# BULLBERRYCPP_REV1_0_2025-06-09.net
KiCad netlist of a schematic drawn in EasyEDA Pro
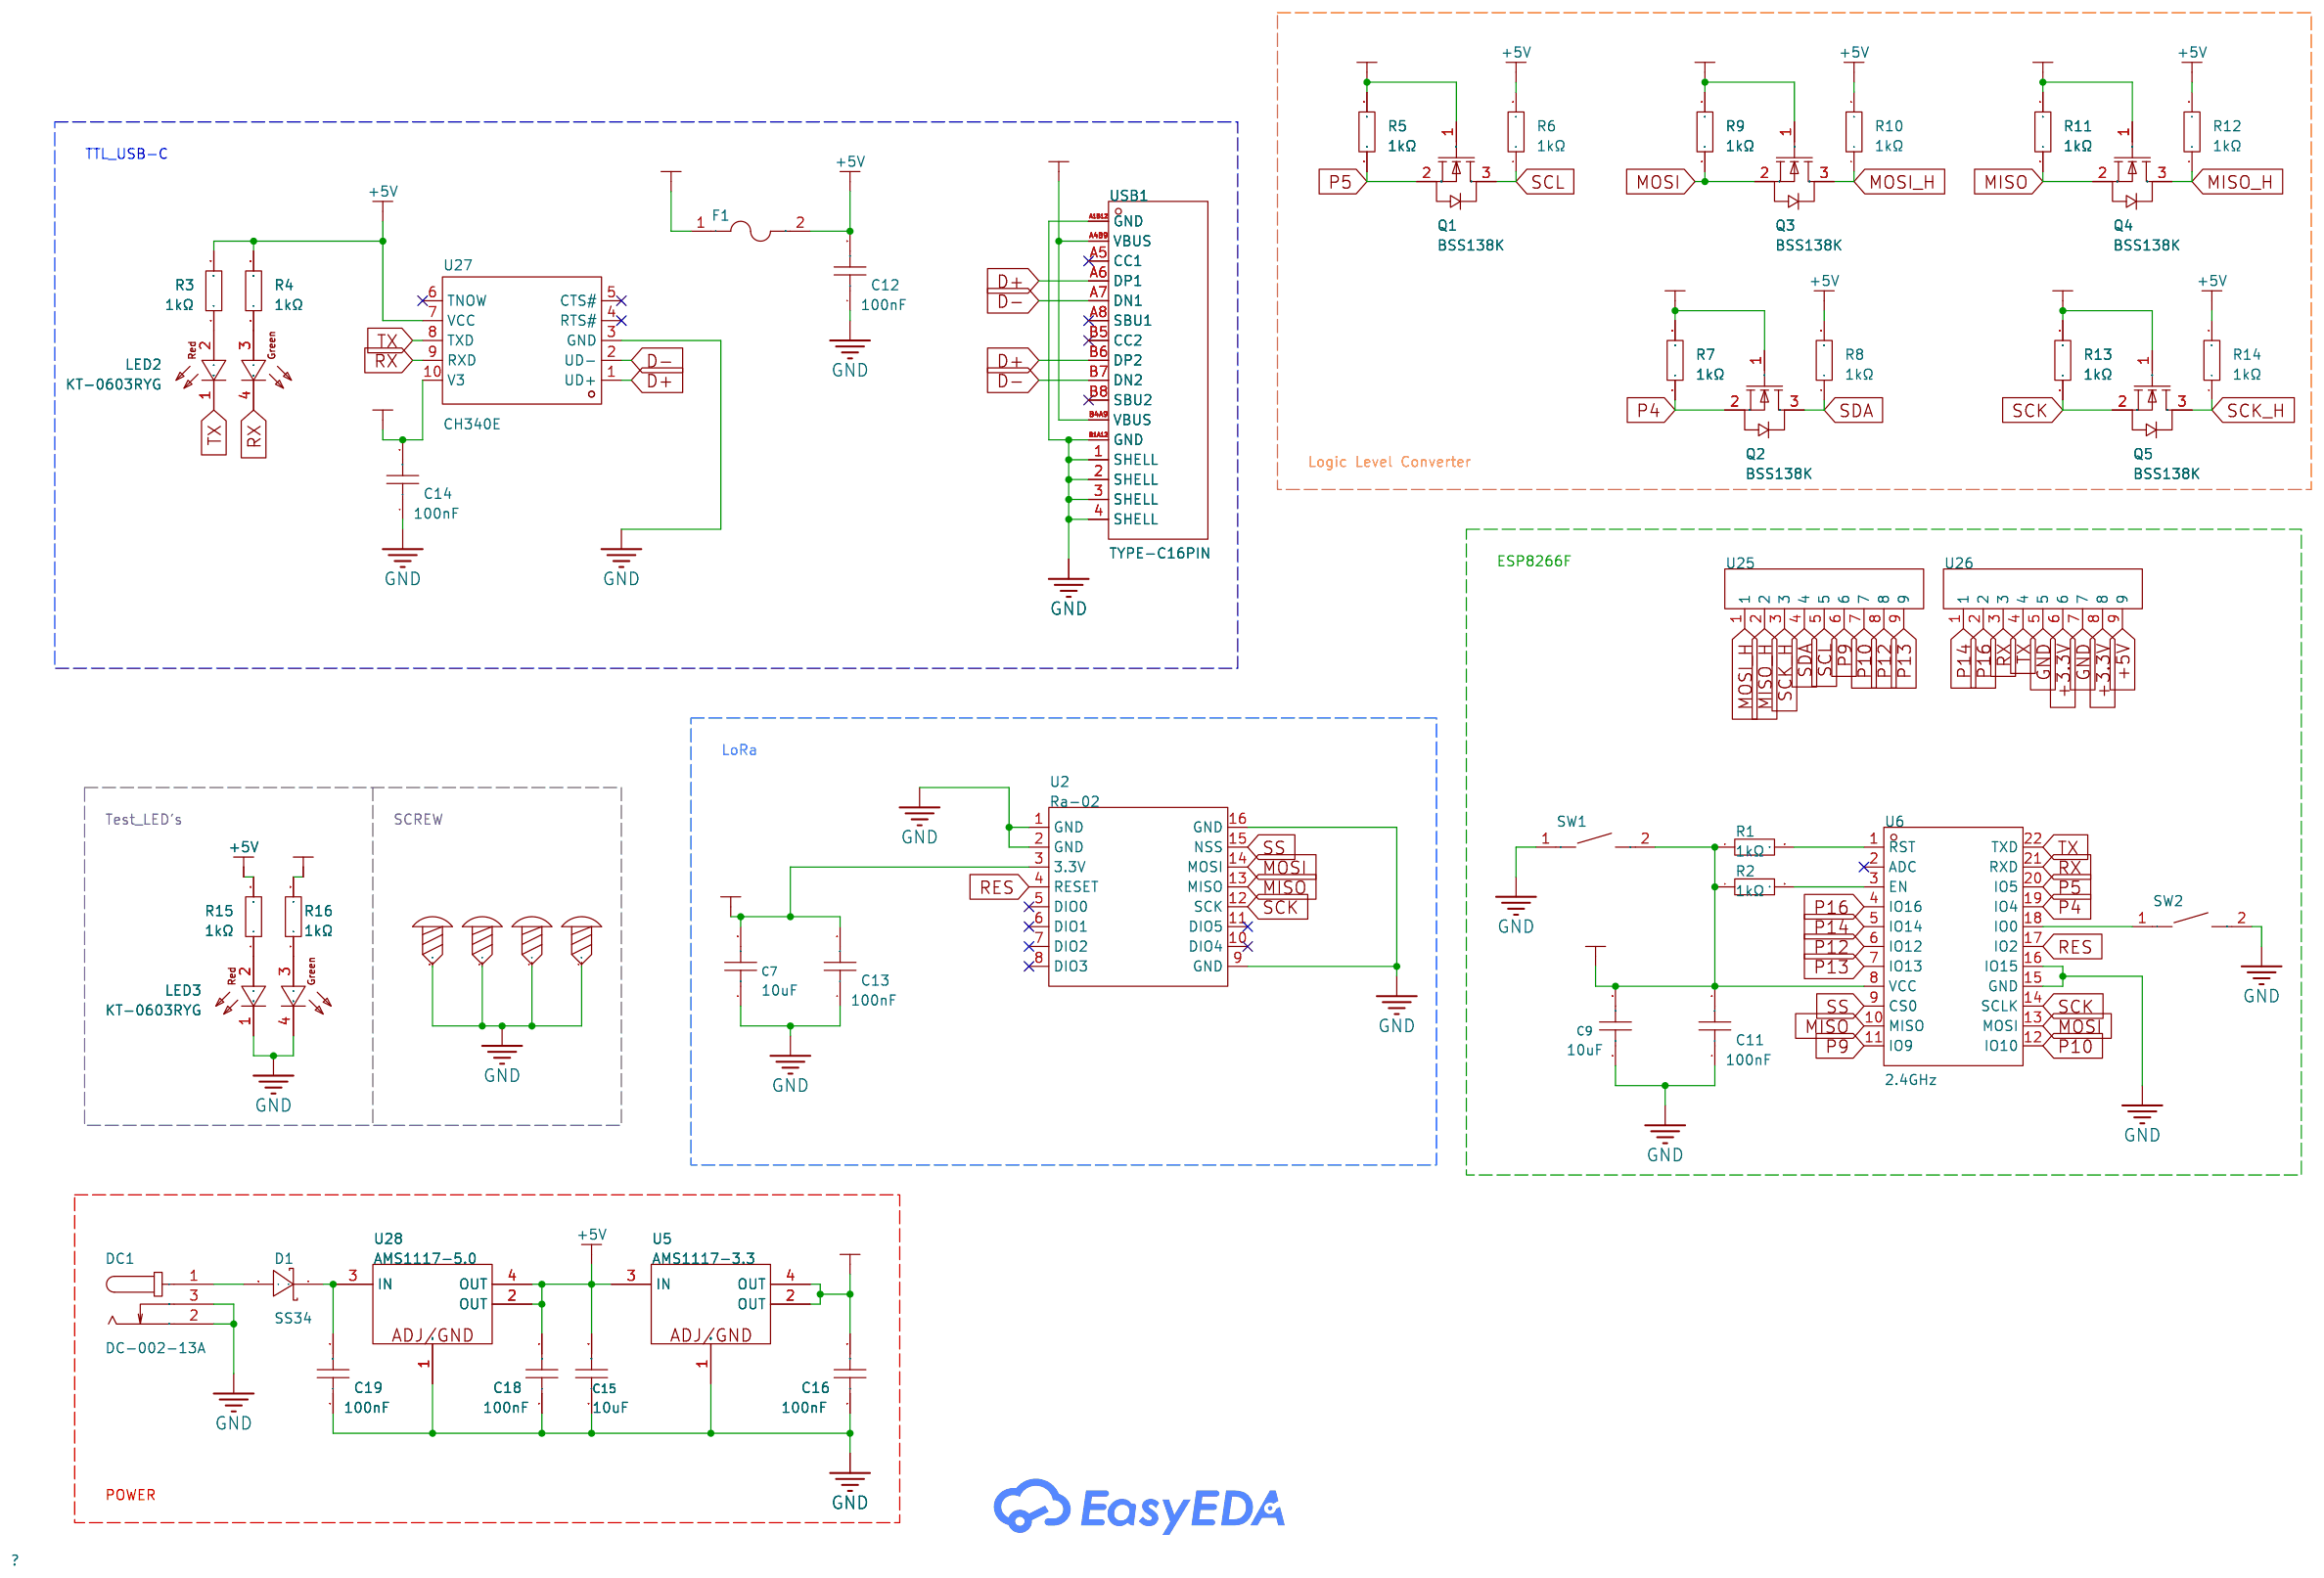
[diagram p0: schematic sheet]

(export (version "E")
  (design (tool "Eeschema 10.0.6"))
  (components
    (comp (ref "C7")
      (value "10uF")
      (footprint "easyedapro:C0603")
      (fields
        (field (name "Manufacturer Part") "CL10A106MA8NRNC")
        (field (name "Manufacturer") "SAMSUNG(三星)")
      )
      (libsource (lib "easyedapro") (part "CL10A106MA8NRNC"))
    )
    (comp (ref "C9")
      (value "10uF")
      (footprint "easyedapro:C0603")
      (fields
        (field (name "Manufacturer Part") "CL10A106MA8NRNC")
        (field (name "Manufacturer") "SAMSUNG(三星)")
      )
      (libsource (lib "easyedapro") (part "CL10A106MA8NRNC"))
    )
    (comp (ref "C11")
      (value "100nF")
      (footprint "easyedapro:C0603")
      (description "Capacitance:100nF Tolerance:±10% Tolerance:±10% Voltage Rating:50V Temperature Coefficient:X7R")
      (fields
        (field (name "Manufacturer Part") "CC0603KRX7R9BB104")
        (field (name "Manufacturer") "YAGEO(国巨)")
      )
      (libsource (lib "easyedapro") (part "CC0603KRX7R9BB104"))
    )
    (comp (ref "C12")
      (value "100nF")
      (footprint "easyedapro:C0603")
      (description "Capacitance:100nF Tolerance:±10% Tolerance:±10% Voltage Rating:50V Temperature Coefficient:X7R")
      (fields
        (field (name "Manufacturer Part") "CC0603KRX7R9BB104")
        (field (name "Manufacturer") "YAGEO(国巨)")
      )
      (libsource (lib "easyedapro") (part "CC0603KRX7R9BB104"))
    )
    (comp (ref "C13")
      (value "100nF")
      (footprint "easyedapro:C0603")
      (description "Capacitance:100nF Tolerance:±10% Tolerance:±10% Voltage Rating:50V Temperature Coefficient:X7R")
      (fields
        (field (name "Manufacturer Part") "CC0603KRX7R9BB104")
        (field (name "Manufacturer") "YAGEO(国巨)")
      )
      (libsource (lib "easyedapro") (part "CC0603KRX7R9BB104"))
    )
    (comp (ref "C14")
      (value "100nF")
      (footprint "easyedapro:C0603")
      (description "Capacitance:100nF Tolerance:±10% Tolerance:±10% Voltage Rating:50V Temperature Coefficient:X7R")
      (fields
        (field (name "Manufacturer Part") "CC0603KRX7R9BB104")
        (field (name "Manufacturer") "YAGEO(国巨)")
      )
      (libsource (lib "easyedapro") (part "CC0603KRX7R9BB104"))
    )
    (comp (ref "C15")
      (value "10uF")
      (footprint "easyedapro:C0603")
      (fields
        (field (name "Manufacturer Part") "CL10A106MA8NRNC")
        (field (name "Manufacturer") "SAMSUNG(三星)")
      )
      (libsource (lib "easyedapro") (part "CL10A106MA8NRNC"))
    )
    (comp (ref "C16")
      (value "100nF")
      (footprint "easyedapro:C0603")
      (description "Capacitance:100nF Tolerance:±10% Tolerance:±10% Voltage Rating:50V Temperature Coefficient:X7R")
      (fields
        (field (name "Manufacturer Part") "CC0603KRX7R9BB104")
        (field (name "Manufacturer") "YAGEO(国巨)")
      )
      (libsource (lib "easyedapro") (part "CC0603KRX7R9BB104"))
    )
    (comp (ref "C18")
      (value "100nF")
      (footprint "easyedapro:C0603")
      (description "Capacitance:100nF Tolerance:±10% Tolerance:±10% Voltage Rating:50V Temperature Coefficient:X7R")
      (fields
        (field (name "Manufacturer Part") "CC0603KRX7R9BB104")
        (field (name "Manufacturer") "YAGEO(国巨)")
      )
      (libsource (lib "easyedapro") (part "CC0603KRX7R9BB104"))
    )
    (comp (ref "C19")
      (value "100nF")
      (footprint "easyedapro:C0603")
      (description "Capacitance:100nF Tolerance:±10% Tolerance:±10% Voltage Rating:50V Temperature Coefficient:X7R")
      (fields
        (field (name "Manufacturer Part") "CC0603KRX7R9BB104")
        (field (name "Manufacturer") "YAGEO(国巨)")
      )
      (libsource (lib "easyedapro") (part "CC0603KRX7R9BB104"))
    )
    (comp (ref "D1")
      (value "SS34")
      (footprint "easyedapro:SMA_L4.3-W2.6-LS5.2-RD")
      (fields (field (name "Manufacturer") "MDD(辰达半导体)"))
      (libsource (lib "easyedapro") (part "SS34_C8678"))
    )
    (comp (ref "DC1")
      (value "DC-002-13A")
      (footprint "easyedapro:DC-IN-TH_DC-002-13A")
      (fields (field (name "Manufacturer") "韩国韩荣"))
      (libsource (lib "easyedapro") (part "DC-002-13A"))
    )
    (comp (ref "F1")
      (value "JFC0603-0500FS")
      (footprint "easyedapro:F0603")
      (fields (field (name "Manufacturer") "JDTfuse(集电通)"))
      (libsource (lib "easyedapro") (part "JFC0603-0500FS"))
    )
    (comp (ref "LED2")
      (value "KT-0603RYG")
      (footprint "easyedapro:LED-SMD_4P-L1.6-W1.5_KT-0603RG")
      (fields (field (name "Manufacturer") "KENTO"))
      (libsource (lib "easyedapro") (part "KT-0603RG"))
    )
    (comp (ref "LED3")
      (value "KT-0603RYG")
      (footprint "easyedapro:LED-SMD_4P-L1.6-W1.5_KT-0603RG")
      (fields (field (name "Manufacturer") "KENTO"))
      (libsource (lib "easyedapro") (part "KT-0603RG"))
    )
    (comp (ref "Q1")
      (value "BSS138K")
      (footprint "easyedapro:SOT-23-3_L2.9-W1.3-P0.95-LS2.4-BR")
      (fields (field (name "Manufacturer") "PAKER(派克微)"))
      (libsource (lib "easyedapro") (part "BSS138K_C18221542"))
    )
    (comp (ref "Q2")
      (value "BSS138K")
      (footprint "easyedapro:SOT-23-3_L2.9-W1.3-P0.95-LS2.4-BR")
      (fields (field (name "Manufacturer") "PAKER(派克微)"))
      (libsource (lib "easyedapro") (part "BSS138K_C18221542"))
    )
    (comp (ref "Q3")
      (value "BSS138K")
      (footprint "easyedapro:SOT-23-3_L2.9-W1.3-P0.95-LS2.4-BR")
      (fields (field (name "Manufacturer") "PAKER(派克微)"))
      (libsource (lib "easyedapro") (part "BSS138K_C18221542"))
    )
    (comp (ref "Q4")
      (value "BSS138K")
      (footprint "easyedapro:SOT-23-3_L2.9-W1.3-P0.95-LS2.4-BR")
      (fields (field (name "Manufacturer") "PAKER(派克微)"))
      (libsource (lib "easyedapro") (part "BSS138K_C18221542"))
    )
    (comp (ref "Q5")
      (value "BSS138K")
      (footprint "easyedapro:SOT-23-3_L2.9-W1.3-P0.95-LS2.4-BR")
      (fields (field (name "Manufacturer") "PAKER(派克微)"))
      (libsource (lib "easyedapro") (part "BSS138K_C18221542"))
    )
    (comp (ref "R1")
      (value "1kΩ")
      (footprint "easyedapro:R0603")
      (fields
        (field (name "Manufacturer Part") "0603WAF1001T5E")
        (field (name "Manufacturer") "UNI-ROYAL(厚声)")
      )
      (libsource (lib "easyedapro") (part "0603WAF1001T5E"))
    )
    (comp (ref "R2")
      (value "1kΩ")
      (footprint "easyedapro:R0603")
      (fields
        (field (name "Manufacturer Part") "0603WAF1001T5E")
        (field (name "Manufacturer") "UNI-ROYAL(厚声)")
      )
      (libsource (lib "easyedapro") (part "0603WAF1001T5E"))
    )
    (comp (ref "R3")
      (value "1kΩ")
      (footprint "easyedapro:R0603")
      (fields
        (field (name "Manufacturer Part") "0603WAF1001T5E")
        (field (name "Manufacturer") "UNI-ROYAL(厚声)")
      )
      (libsource (lib "easyedapro") (part "0603WAF1001T5E"))
    )
    (comp (ref "R4")
      (value "1kΩ")
      (footprint "easyedapro:R0603")
      (fields
        (field (name "Manufacturer Part") "0603WAF1001T5E")
        (field (name "Manufacturer") "UNI-ROYAL(厚声)")
      )
      (libsource (lib "easyedapro") (part "0603WAF1001T5E"))
    )
    (comp (ref "R5")
      (value "1kΩ")
      (footprint "easyedapro:R0603")
      (fields
        (field (name "Manufacturer Part") "0603WAF1001T5E")
        (field (name "Manufacturer") "UNI-ROYAL(厚声)")
      )
      (libsource (lib "easyedapro") (part "0603WAF1001T5E"))
    )
    (comp (ref "R6")
      (value "1kΩ")
      (footprint "easyedapro:R0603")
      (fields
        (field (name "Manufacturer Part") "0603WAF1001T5E")
        (field (name "Manufacturer") "UNI-ROYAL(厚声)")
      )
      (libsource (lib "easyedapro") (part "0603WAF1001T5E"))
    )
    (comp (ref "R7")
      (value "1kΩ")
      (footprint "easyedapro:R0603")
      (fields
        (field (name "Manufacturer Part") "0603WAF1001T5E")
        (field (name "Manufacturer") "UNI-ROYAL(厚声)")
      )
      (libsource (lib "easyedapro") (part "0603WAF1001T5E"))
    )
    (comp (ref "R8")
      (value "1kΩ")
      (footprint "easyedapro:R0603")
      (fields
        (field (name "Manufacturer Part") "0603WAF1001T5E")
        (field (name "Manufacturer") "UNI-ROYAL(厚声)")
      )
      (libsource (lib "easyedapro") (part "0603WAF1001T5E"))
    )
    (comp (ref "R9")
      (value "1kΩ")
      (footprint "easyedapro:R0603")
      (fields
        (field (name "Manufacturer Part") "0603WAF1001T5E")
        (field (name "Manufacturer") "UNI-ROYAL(厚声)")
      )
      (libsource (lib "easyedapro") (part "0603WAF1001T5E"))
    )
    (comp (ref "R10")
      (value "1kΩ")
      (footprint "easyedapro:R0603")
      (fields
        (field (name "Manufacturer Part") "0603WAF1001T5E")
        (field (name "Manufacturer") "UNI-ROYAL(厚声)")
      )
      (libsource (lib "easyedapro") (part "0603WAF1001T5E"))
    )
    (comp (ref "R11")
      (value "1kΩ")
      (footprint "easyedapro:R0603")
      (fields
        (field (name "Manufacturer Part") "0603WAF1001T5E")
        (field (name "Manufacturer") "UNI-ROYAL(厚声)")
      )
      (libsource (lib "easyedapro") (part "0603WAF1001T5E"))
    )
    (comp (ref "R12")
      (value "1kΩ")
      (footprint "easyedapro:R0603")
      (fields
        (field (name "Manufacturer Part") "0603WAF1001T5E")
        (field (name "Manufacturer") "UNI-ROYAL(厚声)")
      )
      (libsource (lib "easyedapro") (part "0603WAF1001T5E"))
    )
    (comp (ref "R13")
      (value "1kΩ")
      (footprint "easyedapro:R0603")
      (fields
        (field (name "Manufacturer Part") "0603WAF1001T5E")
        (field (name "Manufacturer") "UNI-ROYAL(厚声)")
      )
      (libsource (lib "easyedapro") (part "0603WAF1001T5E"))
    )
    (comp (ref "R14")
      (value "1kΩ")
      (footprint "easyedapro:R0603")
      (fields
        (field (name "Manufacturer Part") "0603WAF1001T5E")
        (field (name "Manufacturer") "UNI-ROYAL(厚声)")
      )
      (libsource (lib "easyedapro") (part "0603WAF1001T5E"))
    )
    (comp (ref "R15")
      (value "1kΩ")
      (footprint "easyedapro:R0603")
      (fields
        (field (name "Manufacturer Part") "0603WAF1001T5E")
        (field (name "Manufacturer") "UNI-ROYAL(厚声)")
      )
      (libsource (lib "easyedapro") (part "0603WAF1001T5E"))
    )
    (comp (ref "R16")
      (value "1kΩ")
      (footprint "easyedapro:R0603")
      (fields
        (field (name "Manufacturer Part") "0603WAF1001T5E")
        (field (name "Manufacturer") "UNI-ROYAL(厚声)")
      )
      (libsource (lib "easyedapro") (part "0603WAF1001T5E"))
    )
    (comp (ref "SCREW1")
      (value "~")
      (footprint "easyedapro:Screw-Hole-M2")
      (libsource (lib "easyedapro") (part "Screw-Hole"))
    )
    (comp (ref "SCREW2")
      (value "~")
      (footprint "easyedapro:Screw-Hole-M2")
      (libsource (lib "easyedapro") (part "Screw-Hole"))
    )
    (comp (ref "SCREW3")
      (value "~")
      (footprint "easyedapro:Screw-Hole-M2")
      (libsource (lib "easyedapro") (part "Screw-Hole"))
    )
    (comp (ref "SCREW4")
      (value "~")
      (footprint "easyedapro:Screw-Hole-M2")
      (libsource (lib "easyedapro") (part "Screw-Hole"))
    )
    (comp (ref "SW1")
      (value "TS-1088-AR02016")
      (footprint "easyedapro:SW-SMD_L3.9-W3.0-P4.45")
      (fields (field (name "Manufacturer") "XUNPU(讯普)"))
      (libsource (lib "easyedapro") (part "TS-1088-AR02016"))
    )
    (comp (ref "SW2")
      (value "TS-1088-AR02016")
      (footprint "easyedapro:SW-SMD_L3.9-W3.0-P4.45")
      (fields (field (name "Manufacturer") "XUNPU(讯普)"))
      (libsource (lib "easyedapro") (part "TS-1088-AR02016"))
    )
    (comp (ref "U2")
      (value "Ra-02")
      (footprint "easyedapro:WIRELM-SMD_RA-02-BL")
      (fields (field (name "Manufacturer") "Ai-Thinker(安信可)"))
      (libsource (lib "easyedapro") (part "RA-02"))
    )
    (comp (ref "U5")
      (value "AMS1117-3.3")
      (footprint "easyedapro:SOT-223-3_L6.4-W3.5-P2.30-LS7.0-BR")
      (fields (field (name "Manufacturer") "国芯佳品"))
      (libsource (lib "easyedapro") (part "AMS1117-3.3_C2992570"))
    )
    (comp (ref "U6")
      (value "2.4GHz")
      (footprint "easyedapro:WIRELM-SMD_ESP-12F")
      (fields (field (name "Manufacturer Part") "ESP-12F") (field (name "Manufacturer") "DOIT(四博智联)"))
      (libsource (lib "easyedapro") (part "ESP-12F"))
    )
    (comp (ref "U25")
      (value "DIP插件")
      (footprint "easyedapro:HDR-TH_9P-P2.00-V-F")
      (libsource (lib "easyedapro") (part "DIP-1"))
    )
    (comp (ref "U26")
      (value "DIP插件")
      (footprint "easyedapro:HDR-TH_9P-P2.00-V-F")
      (libsource (lib "easyedapro") (part "DIP-1"))
    )
    (comp (ref "U27")
      (value "CH340E")
      (footprint "easyedapro:MSOP-10_L3.0-W3.0-P0.50-LS5.0-BL")
      (fields (field (name "Manufacturer") "WCH(南京沁恒)"))
      (libsource (lib "easyedapro") (part "CH340E"))
    )
    (comp (ref "U28")
      (value "AMS1117-5.0")
      (footprint "easyedapro:SOT-223-3_L6.4-W3.5-P2.30-LS7.0-BR")
      (fields (field (name "Manufacturer") "国芯佳品"))
      (libsource (lib "easyedapro") (part "AMS1117-5.0_C2992571"))
    )
    (comp (ref "USB1")
      (value "TYPE-C16PIN")
      (footprint "easyedapro:USB-C-SMD_TYPE-C16PIN")
      (fields (field (name "Manufacturer") "SHOU HAN(首韩)"))
      (libsource (lib "easyedapro") (part "TYPE-C16PIN"))
    )
  )
  (nets
    (net (code "1") (name "+3.3V") (class "Default")
      (node (ref "C11") (pin "2") (pinfunction "2_2") (pintype "unspecified"))
      (node (ref "C13") (pin "2") (pinfunction "2_2") (pintype "unspecified"))
      (node (ref "C14") (pin "2") (pinfunction "2_2") (pintype "unspecified"))
      (node (ref "C16") (pin "2") (pinfunction "2_2") (pintype "unspecified"))
      (node (ref "C7") (pin "2") (pinfunction "2_2") (pintype "input"))
      (node (ref "C9") (pin "2") (pinfunction "2_2") (pintype "input"))
      (node (ref "Q1") (pin "1") (pinfunction "G_1") (pintype "unspecified"))
      (node (ref "Q2") (pin "1") (pinfunction "G_1") (pintype "unspecified"))
      (node (ref "Q3") (pin "1") (pinfunction "G_1") (pintype "unspecified"))
      (node (ref "Q4") (pin "1") (pinfunction "G_1") (pintype "unspecified"))
      (node (ref "Q5") (pin "1") (pinfunction "G_1") (pintype "unspecified"))
      (node (ref "R1") (pin "1") (pinfunction "1_1") (pintype "input"))
      (node (ref "R11") (pin "2") (pinfunction "2_2") (pintype "input"))
      (node (ref "R13") (pin "2") (pinfunction "2_2") (pintype "input"))
      (node (ref "R16") (pin "2") (pinfunction "2_2") (pintype "input"))
      (node (ref "R2") (pin "1") (pinfunction "1_1") (pintype "input"))
      (node (ref "R5") (pin "2") (pinfunction "2_2") (pintype "input"))
      (node (ref "R7") (pin "2") (pinfunction "2_2") (pintype "input"))
      (node (ref "R9") (pin "2") (pinfunction "2_2") (pintype "input"))
      (node (ref "SW1") (pin "2") (pinfunction "2_2") (pintype "unspecified"))
      (node (ref "U2") (pin "3") (pinfunction "3.3V_3") (pintype "unspecified"))
      (node (ref "U26") (pin "6") (pinfunction "6_6") (pintype "unspecified"))
      (node (ref "U26") (pin "8") (pinfunction "8_8") (pintype "unspecified"))
      (node (ref "U27") (pin "10") (pinfunction "V3_10") (pintype "unspecified"))
      (node (ref "U5") (pin "2") (pinfunction "OUT_2") (pintype "unspecified"))
      (node (ref "U5") (pin "4") (pinfunction "OUT_4") (pintype "unspecified"))
      (node (ref "U6") (pin "8") (pinfunction "VCC_8") (pintype "unspecified"))
    )
    (net (code "2") (name "+5V") (class "Default")
      (node (ref "C12") (pin "2") (pinfunction "2_2") (pintype "unspecified"))
      (node (ref "C15") (pin "2") (pinfunction "2_2") (pintype "input"))
      (node (ref "C18") (pin "2") (pinfunction "2_2") (pintype "unspecified"))
      (node (ref "F1") (pin "2") (pinfunction "2_2") (pintype "unspecified"))
      (node (ref "R10") (pin "2") (pinfunction "2_2") (pintype "input"))
      (node (ref "R12") (pin "2") (pinfunction "2_2") (pintype "input"))
      (node (ref "R14") (pin "2") (pinfunction "2_2") (pintype "input"))
      (node (ref "R15") (pin "2") (pinfunction "2_2") (pintype "input"))
      (node (ref "R3") (pin "2") (pinfunction "2_2") (pintype "input"))
      (node (ref "R4") (pin "2") (pinfunction "2_2") (pintype "input"))
      (node (ref "R6") (pin "2") (pinfunction "2_2") (pintype "input"))
      (node (ref "R8") (pin "2") (pinfunction "2_2") (pintype "input"))
      (node (ref "U26") (pin "9") (pinfunction "9_9") (pintype "unspecified"))
      (node (ref "U27") (pin "7") (pinfunction "VCC_7") (pintype "unspecified"))
      (node (ref "U28") (pin "2") (pinfunction "OUT_2") (pintype "unspecified"))
      (node (ref "U28") (pin "4") (pinfunction "OUT_4") (pintype "unspecified"))
      (node (ref "U5") (pin "3") (pinfunction "IN_3") (pintype "unspecified"))
    )
    (net (code "3") (name "D+") (class "Default")
      (node (ref "U27") (pin "1") (pinfunction "UD+_1") (pintype "unspecified"))
      (node (ref "USB1") (pin "A6") (pinfunction "DP1_A6") (pintype "unspecified"))
      (node (ref "USB1") (pin "B6") (pinfunction "DP2_B6") (pintype "unspecified"))
    )
    (net (code "4") (name "D-") (class "Default")
      (node (ref "U27") (pin "2") (pinfunction "UD-_2") (pintype "unspecified"))
      (node (ref "USB1") (pin "A7") (pinfunction "DN1_A7") (pintype "unspecified"))
      (node (ref "USB1") (pin "B7") (pinfunction "DN2_B7") (pintype "unspecified"))
    )
    (net (code "5") (name "GND") (class "Default")
      (node (ref "C11") (pin "1") (pinfunction "1_1") (pintype "unspecified"))
      (node (ref "C12") (pin "1") (pinfunction "1_1") (pintype "unspecified"))
      (node (ref "C13") (pin "1") (pinfunction "1_1") (pintype "unspecified"))
      (node (ref "C14") (pin "1") (pinfunction "1_1") (pintype "unspecified"))
      (node (ref "C15") (pin "1") (pinfunction "1_1") (pintype "input"))
      (node (ref "C16") (pin "1") (pinfunction "1_1") (pintype "unspecified"))
      (node (ref "C18") (pin "1") (pinfunction "1_1") (pintype "unspecified"))
      (node (ref "C19") (pin "1") (pinfunction "1_1") (pintype "unspecified"))
      (node (ref "C7") (pin "1") (pinfunction "1_1") (pintype "input"))
      (node (ref "C9") (pin "1") (pinfunction "1_1") (pintype "input"))
      (node (ref "DC1") (pin "2") (pinfunction "2_2") (pintype "unspecified"))
      (node (ref "DC1") (pin "3") (pinfunction "3_3") (pintype "unspecified"))
      (node (ref "LED3") (pin "1") (pinfunction "C_1") (pintype "input"))
      (node (ref "LED3") (pin "4") (pinfunction "C_4") (pintype "input"))
      (node (ref "SCREW1") (pin "1") (pinfunction "1_1") (pintype "input"))
      (node (ref "SCREW2") (pin "1") (pinfunction "1_1") (pintype "input"))
      (node (ref "SCREW3") (pin "1") (pinfunction "1_1") (pintype "input"))
      (node (ref "SCREW4") (pin "1") (pinfunction "1_1") (pintype "input"))
      (node (ref "SW1") (pin "1") (pinfunction "1_1") (pintype "unspecified"))
      (node (ref "SW2") (pin "2") (pinfunction "2_2") (pintype "unspecified"))
      (node (ref "U2") (pin "1") (pinfunction "GND_1") (pintype "unspecified"))
      (node (ref "U2") (pin "16") (pinfunction "GND_16") (pintype "unspecified"))
      (node (ref "U2") (pin "2") (pinfunction "GND_2") (pintype "unspecified"))
      (node (ref "U2") (pin "9") (pinfunction "GND_9") (pintype "unspecified"))
      (node (ref "U26") (pin "5") (pinfunction "5_5") (pintype "unspecified"))
      (node (ref "U26") (pin "7") (pinfunction "7_7") (pintype "unspecified"))
      (node (ref "U27") (pin "3") (pinfunction "GND_3") (pintype "unspecified"))
      (node (ref "U28") (pin "1") (pinfunction "ADJ/GND_1") (pintype "unspecified"))
      (node (ref "U5") (pin "1") (pinfunction "ADJ/GND_1") (pintype "unspecified"))
      (node (ref "U6") (pin "15") (pinfunction "GND_15") (pintype "unspecified"))
      (node (ref "U6") (pin "16") (pinfunction "IO15_16") (pintype "unspecified"))
      (node (ref "USB1") (pin "1") (pinfunction "SHELL_1") (pintype "unspecified"))
      (node (ref "USB1") (pin "2") (pinfunction "SHELL_2") (pintype "unspecified"))
      (node (ref "USB1") (pin "3") (pinfunction "SHELL_3") (pintype "unspecified"))
      (node (ref "USB1") (pin "4") (pinfunction "SHELL_4") (pintype "unspecified"))
      (node (ref "USB1") (pin "A1B12") (pinfunction "GND_A1B12") (pintype "unspecified"))
      (node (ref "USB1") (pin "B1A12") (pinfunction "GND_B1A12") (pintype "unspecified"))
    )
    (net (code "6") (name "MISO") (class "Default")
      (node (ref "Q4") (pin "2") (pinfunction "S_2") (pintype "unspecified"))
      (node (ref "R11") (pin "1") (pinfunction "1_1") (pintype "input"))
      (node (ref "U2") (pin "13") (pinfunction "MISO_13") (pintype "unspecified"))
      (node (ref "U6") (pin "10") (pinfunction "MISO_10") (pintype "unspecified"))
    )
    (net (code "7") (name "MISO_H") (class "Default")
      (node (ref "Q4") (pin "3") (pinfunction "D_3") (pintype "unspecified"))
      (node (ref "R12") (pin "1") (pinfunction "1_1") (pintype "input"))
      (node (ref "U25") (pin "2") (pinfunction "2_2") (pintype "unspecified"))
    )
    (net (code "8") (name "MOSI") (class "Default")
      (node (ref "Q3") (pin "2") (pinfunction "S_2") (pintype "unspecified"))
      (node (ref "R9") (pin "1") (pinfunction "1_1") (pintype "input"))
      (node (ref "U2") (pin "14") (pinfunction "MOSI_14") (pintype "unspecified"))
      (node (ref "U6") (pin "13") (pinfunction "MOSI_13") (pintype "unspecified"))
    )
    (net (code "9") (name "MOSI_H") (class "Default")
      (node (ref "Q3") (pin "3") (pinfunction "D_3") (pintype "unspecified"))
      (node (ref "R10") (pin "1") (pinfunction "1_1") (pintype "input"))
      (node (ref "U25") (pin "1") (pinfunction "1_1") (pintype "unspecified"))
    )
    (net (code "10") (name "Net-(D1-A)") (class "Default")
      (node (ref "D1") (pin "2") (pinfunction "A_2") (pintype "unspecified"))
      (node (ref "DC1") (pin "1") (pinfunction "1_1") (pintype "unspecified"))
    )
    (net (code "11") (name "Net-(D1-K)") (class "Default")
      (node (ref "C19") (pin "2") (pinfunction "2_2") (pintype "unspecified"))
      (node (ref "D1") (pin "1") (pinfunction "K_1") (pintype "unspecified"))
      (node (ref "U28") (pin "3") (pinfunction "IN_3") (pintype "unspecified"))
    )
    (net (code "12") (name "Net-(LED2-A-Pad2)") (class "Default")
      (node (ref "LED2") (pin "2") (pinfunction "A_2") (pintype "input"))
      (node (ref "R3") (pin "1") (pinfunction "1_1") (pintype "input"))
    )
    (net (code "13") (name "Net-(LED2-A-Pad3)") (class "Default")
      (node (ref "LED2") (pin "3") (pinfunction "A_3") (pintype "input"))
      (node (ref "R4") (pin "1") (pinfunction "1_1") (pintype "input"))
    )
    (net (code "14") (name "Net-(LED3-A-Pad2)") (class "Default")
      (node (ref "LED3") (pin "2") (pinfunction "A_2") (pintype "input"))
      (node (ref "R15") (pin "1") (pinfunction "1_1") (pintype "input"))
    )
    (net (code "15") (name "Net-(LED3-A-Pad3)") (class "Default")
      (node (ref "LED3") (pin "3") (pinfunction "A_3") (pintype "input"))
      (node (ref "R16") (pin "1") (pinfunction "1_1") (pintype "input"))
    )
    (net (code "16") (name "Net-(U6-EN)") (class "Default")
      (node (ref "R2") (pin "2") (pinfunction "2_2") (pintype "input"))
      (node (ref "U6") (pin "3") (pinfunction "EN_3") (pintype "unspecified"))
    )
    (net (code "17") (name "Net-(U6-IO0)") (class "Default")
      (node (ref "SW2") (pin "1") (pinfunction "1_1") (pintype "unspecified"))
      (node (ref "U6") (pin "18") (pinfunction "IO0_18") (pintype "unspecified"))
    )
    (net (code "18") (name "Net-(U6-RST)") (class "Default")
      (node (ref "R1") (pin "2") (pinfunction "2_2") (pintype "input"))
      (node (ref "U6") (pin "1") (pinfunction "RST_1") (pintype "unspecified"))
    )
    (net (code "19") (name "P4") (class "Default")
      (node (ref "Q2") (pin "2") (pinfunction "S_2") (pintype "unspecified"))
      (node (ref "R7") (pin "1") (pinfunction "1_1") (pintype "input"))
      (node (ref "U6") (pin "19") (pinfunction "IO4_19") (pintype "unspecified"))
    )
    (net (code "20") (name "P5") (class "Default")
      (node (ref "Q1") (pin "2") (pinfunction "S_2") (pintype "unspecified"))
      (node (ref "R5") (pin "1") (pinfunction "1_1") (pintype "input"))
      (node (ref "U6") (pin "20") (pinfunction "IO5_20") (pintype "unspecified"))
    )
    (net (code "21") (name "P9") (class "Default")
      (node (ref "U25") (pin "6") (pinfunction "6_6") (pintype "unspecified"))
      (node (ref "U6") (pin "11") (pinfunction "IO9_11") (pintype "unspecified"))
    )
    (net (code "22") (name "P10") (class "Default")
      (node (ref "U25") (pin "7") (pinfunction "7_7") (pintype "unspecified"))
      (node (ref "U6") (pin "12") (pinfunction "IO10_12") (pintype "unspecified"))
    )
    (net (code "23") (name "P12") (class "Default")
      (node (ref "U25") (pin "8") (pinfunction "8_8") (pintype "unspecified"))
      (node (ref "U6") (pin "6") (pinfunction "IO12_6") (pintype "unspecified"))
    )
    (net (code "24") (name "P13") (class "Default")
      (node (ref "U25") (pin "9") (pinfunction "9_9") (pintype "unspecified"))
      (node (ref "U6") (pin "7") (pinfunction "IO13_7") (pintype "unspecified"))
    )
    (net (code "25") (name "P14") (class "Default")
      (node (ref "U26") (pin "1") (pinfunction "1_1") (pintype "unspecified"))
      (node (ref "U6") (pin "5") (pinfunction "IO14_5") (pintype "unspecified"))
    )
    (net (code "26") (name "P16") (class "Default")
      (node (ref "U26") (pin "2") (pinfunction "2_2") (pintype "unspecified"))
      (node (ref "U6") (pin "4") (pinfunction "IO16_4") (pintype "unspecified"))
    )
    (net (code "27") (name "RES") (class "Default")
      (node (ref "U2") (pin "4") (pinfunction "RESET_4") (pintype "unspecified"))
      (node (ref "U6") (pin "17") (pinfunction "IO2_17") (pintype "unspecified"))
    )
    (net (code "28") (name "RX") (class "Default")
      (node (ref "LED2") (pin "4") (pinfunction "C_4") (pintype "input"))
      (node (ref "U26") (pin "3") (pinfunction "3_3") (pintype "unspecified"))
      (node (ref "U27") (pin "9") (pinfunction "RXD_9") (pintype "unspecified"))
      (node (ref "U6") (pin "21") (pinfunction "RXD_21") (pintype "unspecified"))
    )
    (net (code "29") (name "SCK") (class "Default")
      (node (ref "Q5") (pin "2") (pinfunction "S_2") (pintype "unspecified"))
      (node (ref "R13") (pin "1") (pinfunction "1_1") (pintype "input"))
      (node (ref "U2") (pin "12") (pinfunction "SCK_12") (pintype "unspecified"))
      (node (ref "U6") (pin "14") (pinfunction "SCLK_14") (pintype "unspecified"))
    )
    (net (code "30") (name "SCK_H") (class "Default")
      (node (ref "Q5") (pin "3") (pinfunction "D_3") (pintype "unspecified"))
      (node (ref "R14") (pin "1") (pinfunction "1_1") (pintype "input"))
      (node (ref "U25") (pin "3") (pinfunction "3_3") (pintype "unspecified"))
    )
    (net (code "31") (name "SCL") (class "Default")
      (node (ref "Q1") (pin "3") (pinfunction "D_3") (pintype "unspecified"))
      (node (ref "R6") (pin "1") (pinfunction "1_1") (pintype "input"))
      (node (ref "U25") (pin "5") (pinfunction "5_5") (pintype "unspecified"))
    )
    (net (code "32") (name "SDA") (class "Default")
      (node (ref "Q2") (pin "3") (pinfunction "D_3") (pintype "unspecified"))
      (node (ref "R8") (pin "1") (pinfunction "1_1") (pintype "input"))
      (node (ref "U25") (pin "4") (pinfunction "4_4") (pintype "unspecified"))
    )
    (net (code "33") (name "SS") (class "Default")
      (node (ref "U2") (pin "15") (pinfunction "NSS_15") (pintype "unspecified"))
      (node (ref "U6") (pin "9") (pinfunction "CS0_9") (pintype "unspecified"))
    )
    (net (code "34") (name "TX") (class "Default")
      (node (ref "LED2") (pin "1") (pinfunction "C_1") (pintype "input"))
      (node (ref "U26") (pin "4") (pinfunction "4_4") (pintype "unspecified"))
      (node (ref "U27") (pin "8") (pinfunction "TXD_8") (pintype "unspecified"))
      (node (ref "U6") (pin "22") (pinfunction "TXD_22") (pintype "unspecified"))
    )
    (net (code "35") (name "VBUS") (class "Default")
      (node (ref "F1") (pin "1") (pinfunction "1_1") (pintype "unspecified"))
      (node (ref "USB1") (pin "A4B9") (pinfunction "VBUS_A4B9") (pintype "unspecified"))
      (node (ref "USB1") (pin "B4A9") (pinfunction "VBUS_B4A9") (pintype "unspecified"))
    )
    (net (code "36") (name "unconnected-(U2-DIO0-Pad5)") (class "Default")
      (node (ref "U2") (pin "5") (pinfunction "DIO0_5") (pintype "unspecified+no_connect"))
    )
    (net (code "37") (name "unconnected-(U2-DIO1-Pad6)") (class "Default")
      (node (ref "U2") (pin "6") (pinfunction "DIO1_6") (pintype "unspecified+no_connect"))
    )
    (net (code "38") (name "unconnected-(U2-DIO2-Pad7)") (class "Default")
      (node (ref "U2") (pin "7") (pinfunction "DIO2_7") (pintype "unspecified+no_connect"))
    )
    (net (code "39") (name "unconnected-(U2-DIO3-Pad8)") (class "Default")
      (node (ref "U2") (pin "8") (pinfunction "DIO3_8") (pintype "unspecified+no_connect"))
    )
    (net (code "40") (name "unconnected-(U2-DIO4-Pad10)") (class "Default")
      (node (ref "U2") (pin "10") (pinfunction "DIO4_10") (pintype "unspecified+no_connect"))
    )
    (net (code "41") (name "unconnected-(U2-DIO5-Pad11)") (class "Default")
      (node (ref "U2") (pin "11") (pinfunction "DIO5_11") (pintype "unspecified+no_connect"))
    )
    (net (code "42") (name "unconnected-(U6-ADC-Pad2)") (class "Default")
      (node (ref "U6") (pin "2") (pinfunction "ADC_2") (pintype "unspecified+no_connect"))
    )
    (net (code "43") (name "unconnected-(U27-CTS#-Pad5)") (class "Default")
      (node (ref "U27") (pin "5") (pinfunction "CTS#_5") (pintype "unspecified+no_connect"))
    )
    (net (code "44") (name "unconnected-(U27-RTS#-Pad4)") (class "Default")
      (node (ref "U27") (pin "4") (pinfunction "RTS#_4") (pintype "unspecified+no_connect"))
    )
    (net (code "45") (name "unconnected-(U27-TNOW-Pad6)") (class "Default")
      (node (ref "U27") (pin "6") (pinfunction "TNOW_6") (pintype "unspecified+no_connect"))
    )
    (net (code "46") (name "unconnected-(USB1-CC1-PadA5)") (class "Default")
      (node (ref "USB1") (pin "A5") (pinfunction "CC1_A5") (pintype "unspecified+no_connect"))
    )
    (net (code "47") (name "unconnected-(USB1-CC2-PadB5)") (class "Default")
      (node (ref "USB1") (pin "B5") (pinfunction "CC2_B5") (pintype "unspecified+no_connect"))
    )
    (net (code "48") (name "unconnected-(USB1-SBU1-PadA8)") (class "Default")
      (node (ref "USB1") (pin "A8") (pinfunction "SBU1_A8") (pintype "unspecified+no_connect"))
    )
    (net (code "49") (name "unconnected-(USB1-SBU2-PadB8)") (class "Default")
      (node (ref "USB1") (pin "B8") (pinfunction "SBU2_B8") (pintype "unspecified+no_connect"))
    )
  )
)
